# 6_-CH340C.net
KiCad netlist of a schematic drawn in Altium Designer
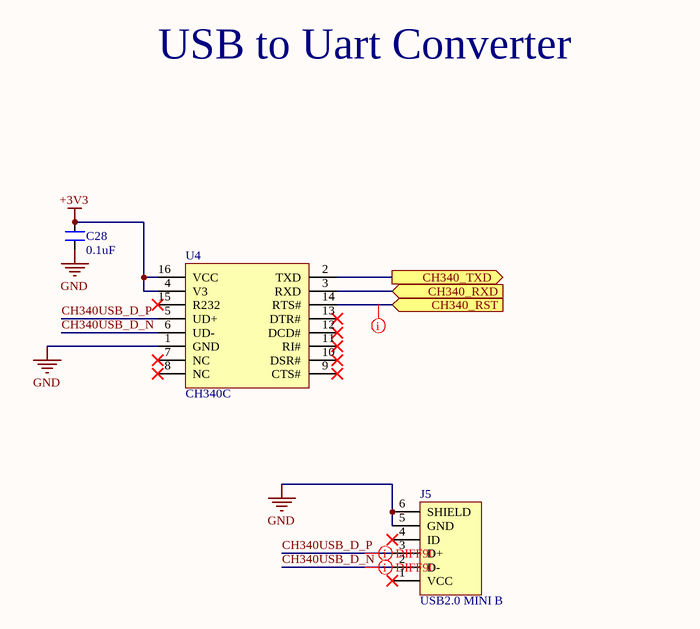
[diagram p0: [6]-CH340C.SchDoc]

(export (version "E")
  (design (tool "Eeschema 10.0.6"))
  (components
    (comp (ref "C28")
      (value "0.1uF")
      (footprint "CAP_0805")
      (description "0.1µF ±10% 50V Ceramic Capacitor X7R 0805 (2012 Metric)")
      (fields
        (field (name "MANUFACTURER") "Samsung")
        (field (name "MANUFACTURER PART NUMBER") "CL21B104KBCNNNC")
      )
      (libsource (lib "ESTEEMPCBLIB") (part "CAP_0.1uF-50V-10%-0805"))
    )
    (comp (ref "J5")
      (value "USB2.0 MINI B")
      (footprint "CON_690-005-299-043")
      (description "USB - mini B USB 2.0 Receptacle Connector 5 Position Surface Mount, Right Angle")
      (fields
        (field (name "MANUFACTURER") "EDAC")
        (field (name "MANUFACTURER PART NUMBER") "690-005-299-043")
      )
      (libsource (lib "ESTEEMPCBLIB") (part "CON_USB2.0-MINIB-SMD"))
    )
    (comp (ref "U4")
      (value "CH340C")
      (footprint "SOIC16_50_284_25X90_SMT")
      (description "USB Bridge, USB to UART USB 2.0 UART Interface")
      (fields (field (name "MANUFACTURER") "Olimex"))
      (libsource (lib "ESTEEMPCBLIB") (part "IC_CH340C"))
    )
  )
  (nets
    (net (code "1") (name "+3V3") (class "Default")
      (node (ref "C28") (pin "2") (pinfunction "2_2") (pintype "passive"))
      (node (ref "U4") (pin "16") (pinfunction "VCC_16") (pintype "passive"))
      (node (ref "U4") (pin "4") (pinfunction "V3_4") (pintype "passive"))
    )
    (net (code "2") (name "/CH340USB_D_N") (class "Default")
      (node (ref "J5") (pin "2") (pinfunction "D-_2") (pintype "passive"))
      (node (ref "U4") (pin "6") (pinfunction "UD-_6") (pintype "passive"))
    )
    (net (code "3") (name "/CH340USB_D_P") (class "Default")
      (node (ref "J5") (pin "3") (pinfunction "D+_3") (pintype "passive"))
      (node (ref "U4") (pin "5") (pinfunction "UD+_5") (pintype "passive"))
    )
    (net (code "4") (name "/CH340_RST") (class "Default")
      (node (ref "U4") (pin "14") (pinfunction "RTS#_14") (pintype "passive"))
    )
    (net (code "5") (name "/CH340_RXD") (class "Default")
      (node (ref "U4") (pin "3") (pinfunction "RXD_3") (pintype "passive"))
    )
    (net (code "6") (name "/CH340_TXD") (class "Default")
      (node (ref "U4") (pin "2") (pinfunction "TXD_2") (pintype "passive"))
    )
    (net (code "7") (name "GND") (class "Default")
      (node (ref "C28") (pin "1") (pinfunction "1_1") (pintype "passive"))
      (node (ref "J5") (pin "5") (pinfunction "GND_5") (pintype "passive"))
      (node (ref "J5") (pin "6") (pinfunction "SHIELD_6") (pintype "passive"))
      (node (ref "U4") (pin "1") (pinfunction "GND_1") (pintype "passive"))
    )
    (net (code "8") (name "unconnected-(J5-ID-Pad4)") (class "Default")
      (node (ref "J5") (pin "4") (pinfunction "ID_4") (pintype "passive+no_connect"))
    )
    (net (code "9") (name "unconnected-(J5-VCC-Pad1)") (class "Default")
      (node (ref "J5") (pin "1") (pinfunction "VCC_1") (pintype "passive+no_connect"))
    )
    (net (code "10") (name "unconnected-(U4-CTS#-Pad9)") (class "Default")
      (node (ref "U4") (pin "9") (pinfunction "CTS#_9") (pintype "passive+no_connect"))
    )
    (net (code "11") (name "unconnected-(U4-DCD#-Pad12)") (class "Default")
      (node (ref "U4") (pin "12") (pinfunction "DCD#_12") (pintype "passive+no_connect"))
    )
    (net (code "12") (name "unconnected-(U4-DSR#-Pad10)") (class "Default")
      (node (ref "U4") (pin "10") (pinfunction "DSR#_10") (pintype "passive+no_connect"))
    )
    (net (code "13") (name "unconnected-(U4-DTR#-Pad13)") (class "Default")
      (node (ref "U4") (pin "13") (pinfunction "DTR#_13") (pintype "passive+no_connect"))
    )
    (net (code "14") (name "unconnected-(U4-NC-Pad7)") (class "Default")
      (node (ref "U4") (pin "7") (pinfunction "NC_7") (pintype "passive+no_connect"))
    )
    (net (code "15") (name "unconnected-(U4-NC-Pad8)") (class "Default")
      (node (ref "U4") (pin "8") (pinfunction "NC_8") (pintype "passive+no_connect"))
    )
    (net (code "16") (name "unconnected-(U4-R232-Pad15)") (class "Default")
      (node (ref "U4") (pin "15") (pinfunction "R232_15") (pintype "passive+no_connect"))
    )
    (net (code "17") (name "unconnected-(U4-RI#-Pad11)") (class "Default")
      (node (ref "U4") (pin "11") (pinfunction "RI#_11") (pintype "passive+no_connect"))
    )
  )
)
